# LiPo_Charger.net
KiCad netlist of a schematic drawn in Altium Designer
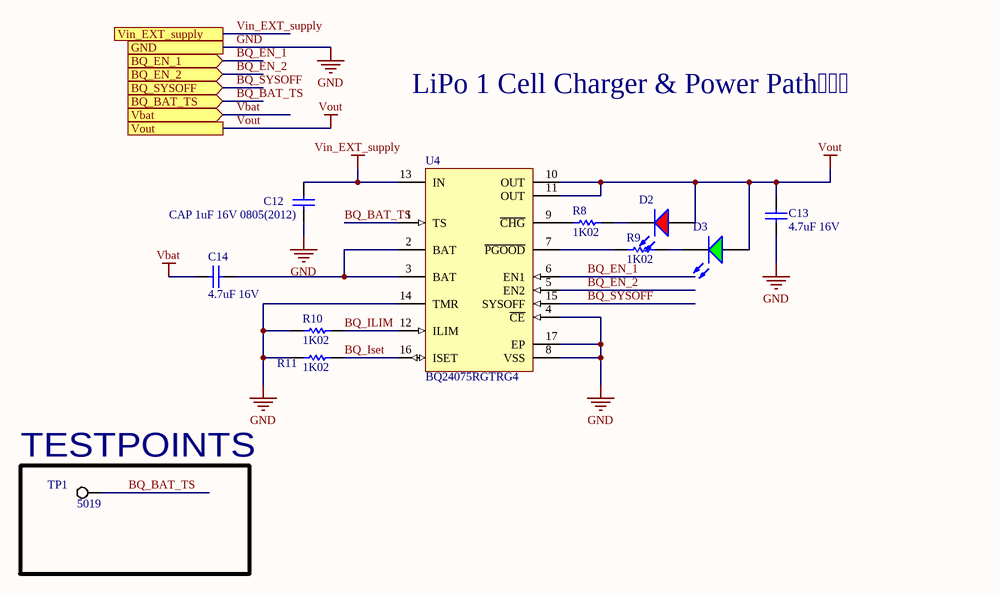
[diagram p0: LiPo_Charger.SchDoc]

(export (version "E")
  (design (tool "Eeschema 10.0.6"))
  (components
    (comp (ref "C12")
      (value "CAP 1uF 16V 0805(2012)")
      (footprint "CAPC0805(2012)100_L")
      (description "CAP 1uF 16V ±20% 0805 (2012 Metric) Thickness 1mm SMD")
      (fields (field (name "TOLERANCE") "Â±20%"))
      (libsource (lib "Altium Content Vault") (part "CAP"))
    )
    (comp (ref "C13")
      (value "4.7uF 16V")
      (footprint "CAPC0805(2012)145_N")
      (description "CAP 4.7uF 16V ±10% 0805 (2012 Metric) Thickness 1.45mm SMD")
      (fields (field (name "TOLERANCE") "Â±10%"))
      (libsource (lib "Altium Content Vault") (part "CAP"))
    )
    (comp (ref "C14")
      (value "4.7uF 16V")
      (footprint "CAPC0805(2012)145_N")
      (description "CAP 4.7uF 16V ±10% 0805 (2012 Metric) Thickness 1.45mm SMD")
      (fields (field (name "TOLERANCE") "Â±10%"))
      (libsource (lib "Altium Content Vault") (part "CAP"))
    )
    (comp (ref "D2")
      (value "~")
      (footprint "LTST-C170CKT_V")
      (description "LED RED CLEAR 0805 SMD")
      (fields (field (name "MANUFACTURER") "Lite-On") (field (name "PARTNUMBER") "LTST-C170CKT"))
      (libsource (lib "Altium Content Vault") (part "LED_RED_AC"))
    )
    (comp (ref "D3")
      (value "~")
      (footprint "LTST-C170GKT_V")
      (description "LED Uni-Color Green, 100 mW, 120 mA, -55 to 85 degC, 2-Pin SMD, RoHS, Tape and Reel")
      (libsource (lib "Altium Content Vault") (part "LED-GREEN-AK-2"))
    )
    (comp (ref "R8")
      (value "1K02")
      (footprint "RESC0603(1608)_N")
      (description "1K02 0.1W 1% 0603 (1608 Metric)  SMD")
      (fields (field (name "POWER") "0.1 W") (field (name "TOLERANCE") "1 %"))
      (libsource (lib "Altium Content Vault") (part "RES"))
    )
    (comp (ref "R9")
      (value "1K02")
      (footprint "RESC0603(1608)_N")
      (description "1K02 0.1W 1% 0603 (1608 Metric)  SMD")
      (fields (field (name "POWER") "0.1 W") (field (name "TOLERANCE") "1 %"))
      (libsource (lib "Altium Content Vault") (part "RES"))
    )
    (comp (ref "R10")
      (value "1K02")
      (footprint "RESC0603(1608)_N")
      (description "1K02 0.1W 1% 0603 (1608 Metric)  SMD")
      (fields (field (name "POWER") "0.1 W") (field (name "TOLERANCE") "1 %"))
      (libsource (lib "Altium Content Vault") (part "RES"))
    )
    (comp (ref "R11")
      (value "1K02")
      (footprint "RESC0603(1608)_N")
      (description "1K02 0.1W 1% 0603 (1608 Metric)  SMD")
      (fields (field (name "POWER") "0.1 W") (field (name "TOLERANCE") "1 %"))
      (libsource (lib "Altium Content Vault") (part "RES"))
    )
    (comp (ref "TP1")
      (value "5019")
      (footprint "KSTN-5019_V")
      (description "Test Point, 1 Position SMD, RoHS, Tape and Reel")
      (libsource (lib "Altium Content Vault") (part "TESTPOINT_WHITE"))
    )
    (comp (ref "U4")
      (value "BQ24075RGTRG4")
      (footprint "RGT16-1700X1700TP")
      (fields (field (name "MANUFACTURER") "Texas Instruments"))
      (libsource (lib "Altium Content Vault") (part "TI-BQ24075RGT16-1700X1700TP"))
    )
  )
  (nets
    (net (code "1") (name "/BQ_BAT_TS") (class "Default")
      (node (ref "TP1") (pin "1") (pinfunction "1_1") (pintype "passive"))
      (node (ref "U4") (pin "1") (pinfunction "TS_1") (pintype "input"))
    )
    (net (code "2") (name "/BQ_EN_1") (class "Default")
      (node (ref "U4") (pin "6") (pinfunction "EN1_6") (pintype "input"))
    )
    (net (code "3") (name "/BQ_EN_2") (class "Default")
      (node (ref "U4") (pin "5") (pinfunction "EN2_5") (pintype "input"))
    )
    (net (code "4") (name "/BQ_ILIM") (class "Default")
      (node (ref "R10") (pin "2") (pinfunction "2_2") (pintype "passive"))
      (node (ref "U4") (pin "12") (pinfunction "ILIM_12") (pintype "input"))
    )
    (net (code "5") (name "/BQ_Iset") (class "Default")
      (node (ref "R11") (pin "2") (pinfunction "2_2") (pintype "passive"))
      (node (ref "U4") (pin "16") (pinfunction "ISET_16") (pintype "bidirectional"))
    )
    (net (code "6") (name "/BQ_SYSOFF") (class "Default")
      (node (ref "U4") (pin "15") (pinfunction "SYSOFF_15") (pintype "input"))
    )
    (net (code "7") (name "GND") (class "Default")
      (node (ref "C12") (pin "1") (pinfunction "1_1") (pintype "passive"))
      (node (ref "C13") (pin "1") (pinfunction "1_1") (pintype "passive"))
      (node (ref "R10") (pin "1") (pinfunction "1_1") (pintype "passive"))
      (node (ref "R11") (pin "1") (pinfunction "1_1") (pintype "passive"))
      (node (ref "U4") (pin "14") (pinfunction "TMR_14") (pintype "passive"))
      (node (ref "U4") (pin "17") (pinfunction "EP_17") (pintype "power_in"))
      (node (ref "U4") (pin "4") (pinfunction "~{CE}_4") (pintype "input"))
      (node (ref "U4") (pin "8") (pinfunction "VSS_8") (pintype "power_in"))
    )
    (net (code "8") (name "Net-(C14-Pad1)") (class "Default")
      (node (ref "C14") (pin "1") (pinfunction "1_1") (pintype "passive"))
      (node (ref "U4") (pin "2") (pinfunction "BAT_2") (pintype "power_in"))
      (node (ref "U4") (pin "3") (pinfunction "BAT_3") (pintype "power_in"))
    )
    (net (code "9") (name "Net-(D2-PadC)") (class "Default")
      (node (ref "D2") (pin "C") (pinfunction "C_C") (pintype "passive"))
      (node (ref "R8") (pin "2") (pinfunction "2_2") (pintype "passive"))
    )
    (net (code "10") (name "Net-(D3-K)") (class "Default")
      (node (ref "D3") (pin "2") (pinfunction "K_2") (pintype "passive"))
      (node (ref "R9") (pin "2") (pinfunction "2_2") (pintype "passive"))
    )
    (net (code "11") (name "Net-(U4-~{CHG})") (class "Default")
      (node (ref "R8") (pin "1") (pinfunction "1_1") (pintype "passive"))
      (node (ref "U4") (pin "9") (pinfunction "~{CHG}_9") (pintype "tri_state"))
    )
    (net (code "12") (name "Net-(U4-~{PGOOD})") (class "Default")
      (node (ref "R9") (pin "1") (pinfunction "1_1") (pintype "passive"))
      (node (ref "U4") (pin "7") (pinfunction "~{PGOOD}_7") (pintype "tri_state"))
    )
    (net (code "13") (name "Vbat") (class "Default")
      (node (ref "C14") (pin "2") (pinfunction "2_2") (pintype "passive"))
    )
    (net (code "14") (name "Vin_EXT_supply") (class "Default")
      (node (ref "C12") (pin "2") (pinfunction "2_2") (pintype "passive"))
      (node (ref "U4") (pin "13") (pinfunction "IN_13") (pintype "power_in"))
    )
    (net (code "15") (name "Vout") (class "Default")
      (node (ref "C13") (pin "2") (pinfunction "2_2") (pintype "passive"))
      (node (ref "D2") (pin "A") (pinfunction "A_A") (pintype "passive"))
      (node (ref "D3") (pin "1") (pinfunction "A_1") (pintype "passive"))
      (node (ref "U4") (pin "10") (pinfunction "OUT_10") (pintype "power_in"))
      (node (ref "U4") (pin "11") (pinfunction "OUT_11") (pintype "power_in"))
    )
  )
)
